# 03_-_RS232_JOYSTICK.net
KiCad netlist of a schematic drawn in Altium Designer
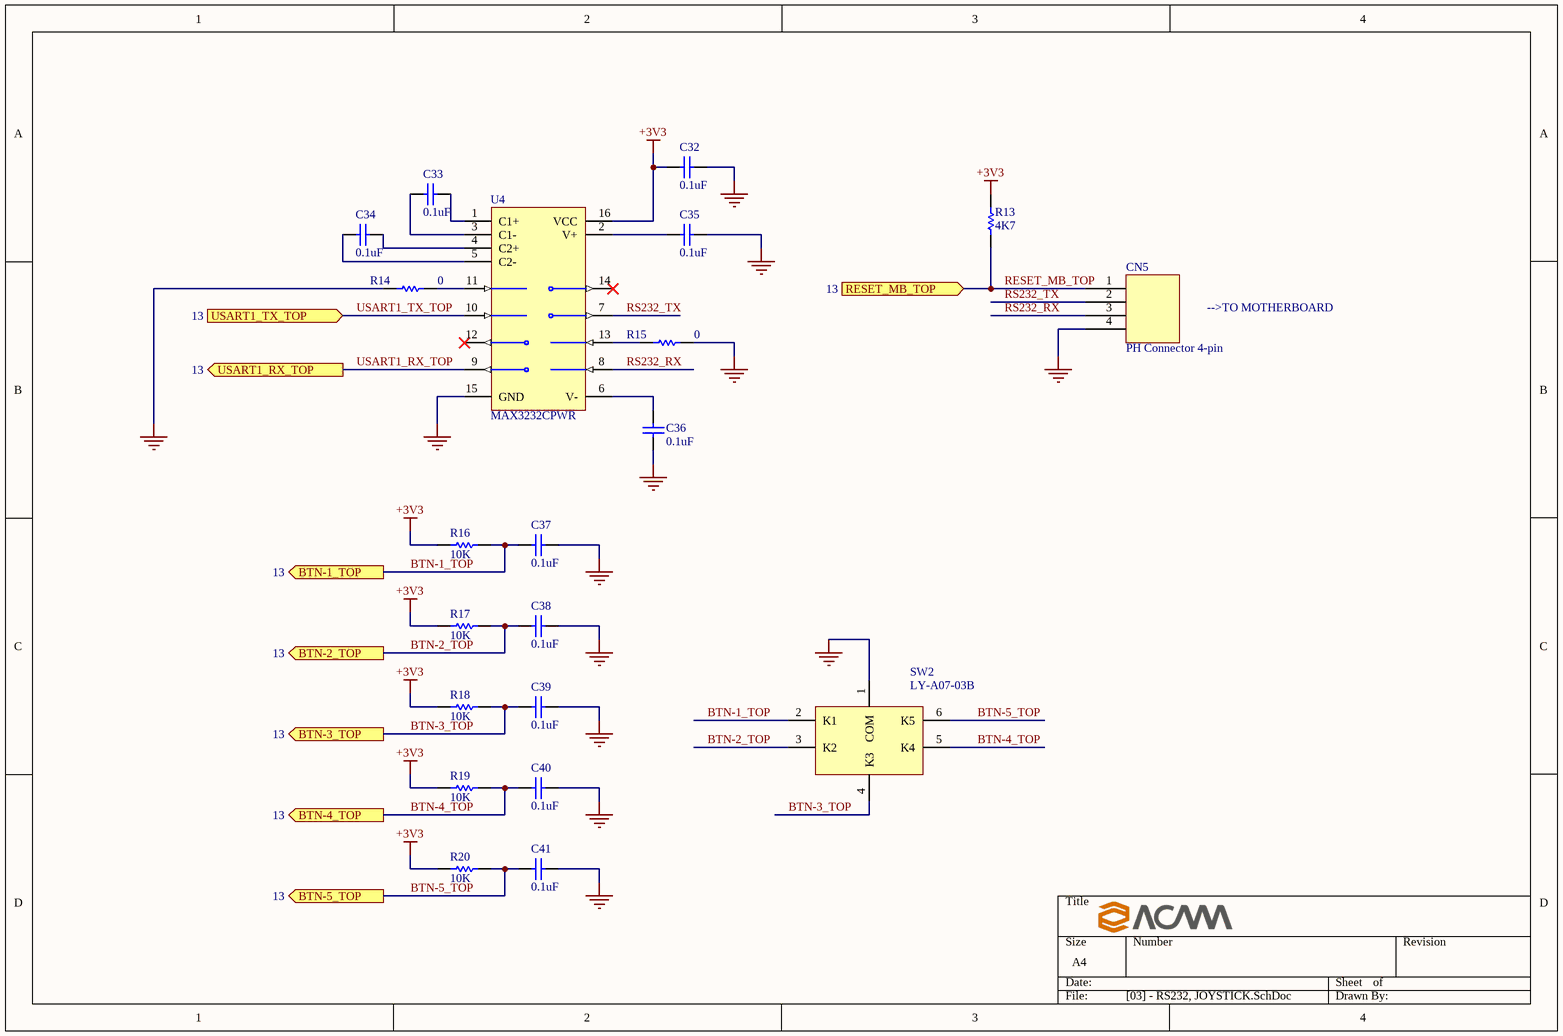
[diagram p0: [03] - RS232, JOYSTICK.SchDoc]

(export (version "E")
  (design (tool "Eeschema 10.0.6"))
  (components
    (comp (ref "C32")
      (value "0.1uF")
      (footprint "0805_C_AUTO")
      (description "Non-Pol SMD Capacitor")
      (libsource (lib "Farzan Custom Library") (part "Cap SMD"))
    )
    (comp (ref "C33")
      (value "0.1uF")
      (footprint "0805_C_AUTO")
      (description "Non-Pol SMD Capacitor")
      (libsource (lib "Farzan Custom Library") (part "Cap SMD"))
    )
    (comp (ref "C34")
      (value "0.1uF")
      (footprint "0805_C_AUTO")
      (description "Non-Pol SMD Capacitor")
      (libsource (lib "Farzan Custom Library") (part "Cap SMD"))
    )
    (comp (ref "C35")
      (value "0.1uF")
      (footprint "0805_C_AUTO")
      (description "Non-Pol SMD Capacitor")
      (libsource (lib "Farzan Custom Library") (part "Cap SMD"))
    )
    (comp (ref "C36")
      (value "0.1uF")
      (footprint "0805_C_AUTO")
      (description "Non-Pol SMD Capacitor")
      (libsource (lib "Farzan Custom Library") (part "Cap SMD"))
    )
    (comp (ref "C37")
      (value "0.1uF")
      (footprint "0805_C_AUTO")
      (description "Non-Pol SMD Capacitor")
      (libsource (lib "Farzan Custom Library") (part "Cap SMD"))
    )
    (comp (ref "C38")
      (value "0.1uF")
      (footprint "0805_C_AUTO")
      (description "Non-Pol SMD Capacitor")
      (libsource (lib "Farzan Custom Library") (part "Cap SMD"))
    )
    (comp (ref "C39")
      (value "0.1uF")
      (footprint "0805_C_AUTO")
      (description "Non-Pol SMD Capacitor")
      (libsource (lib "Farzan Custom Library") (part "Cap SMD"))
    )
    (comp (ref "C40")
      (value "0.1uF")
      (footprint "0805_C_AUTO")
      (description "Non-Pol SMD Capacitor")
      (libsource (lib "Farzan Custom Library") (part "Cap SMD"))
    )
    (comp (ref "C41")
      (value "0.1uF")
      (footprint "0805_C_AUTO")
      (description "Non-Pol SMD Capacitor")
      (libsource (lib "Farzan Custom Library") (part "Cap SMD"))
    )
    (comp (ref "CN5")
      (value "PH Connector 4-pin")
      (footprint "PH_4PIN")
      (description "PH Connector , 4 pin, 2mm pitch, straight")
      (libsource (lib "Farzan Custom Library") (part "PH Connector 4-pin"))
    )
    (comp (ref "R13")
      (value "4K7")
      (footprint "0805_R_AUTO")
      (description "SMD Resistor")
      (fields (field (name "TOLERANCE") "5%"))
      (libsource (lib "Farzan Custom Library") (part "Res SMD"))
    )
    (comp (ref "R14")
      (value "0")
      (footprint "0805_R_AUTO")
      (description "SMD Resistor")
      (fields (field (name "TOLERANCE") "5%"))
      (libsource (lib "Farzan Custom Library") (part "Res SMD"))
    )
    (comp (ref "R15")
      (value "0")
      (footprint "0805_R_AUTO")
      (description "SMD Resistor")
      (fields (field (name "TOLERANCE") "5%"))
      (libsource (lib "Farzan Custom Library") (part "Res SMD"))
    )
    (comp (ref "R16")
      (value "10K")
      (footprint "0805_R_AUTO")
      (description "SMD Resistor")
      (fields (field (name "TOLERANCE") "5%"))
      (libsource (lib "Farzan Custom Library") (part "Res SMD"))
    )
    (comp (ref "R17")
      (value "10K")
      (footprint "0805_R_AUTO")
      (description "SMD Resistor")
      (fields (field (name "TOLERANCE") "5%"))
      (libsource (lib "Farzan Custom Library") (part "Res SMD"))
    )
    (comp (ref "R18")
      (value "10K")
      (footprint "0805_R_AUTO")
      (description "SMD Resistor")
      (fields (field (name "TOLERANCE") "5%"))
      (libsource (lib "Farzan Custom Library") (part "Res SMD"))
    )
    (comp (ref "R19")
      (value "10K")
      (footprint "0805_R_AUTO")
      (description "SMD Resistor")
      (fields (field (name "TOLERANCE") "5%"))
      (libsource (lib "Farzan Custom Library") (part "Res SMD"))
    )
    (comp (ref "R20")
      (value "10K")
      (footprint "0805_R_AUTO")
      (description "SMD Resistor")
      (fields (field (name "TOLERANCE") "5%"))
      (libsource (lib "Farzan Custom Library") (part "Res SMD"))
    )
    (comp (ref "SW2")
      (value "LY-A07-03B")
      (footprint "LY-A07-03B")
      (description "5 Way Key")
      (libsource (lib "Farzan Custom Library") (part "KEY 5W"))
    )
    (comp (ref "U4")
      (value "MAX3232CPWR")
      (footprint "TSSOP-16")
      (description "3.0V TO 5.5V, Low-Power, up to 1Mbps, True RS-232 Transceiver Using Four 0.1µF External Capacitor")
      (libsource (lib "Farzan Custom Library") (part "MAX3232"))
    )
  )
  (nets
    (net (code "1") (name "+3V3") (class "Default")
      (node (ref "C32") (pin "2") (pinfunction "2_2") (pintype "passive"))
      (node (ref "R13") (pin "1") (pinfunction "1_1") (pintype "passive"))
      (node (ref "R16") (pin "2") (pinfunction "2_2") (pintype "passive"))
      (node (ref "R17") (pin "2") (pinfunction "2_2") (pintype "passive"))
      (node (ref "R18") (pin "2") (pinfunction "2_2") (pintype "passive"))
      (node (ref "R19") (pin "2") (pinfunction "2_2") (pintype "passive"))
      (node (ref "R20") (pin "2") (pinfunction "2_2") (pintype "passive"))
      (node (ref "U4") (pin "16") (pinfunction "VCC_16") (pintype "power_in"))
    )
    (net (code "2") (name "/BTN-1_TOP") (class "Default")
      (node (ref "C37") (pin "2") (pinfunction "2_2") (pintype "passive"))
      (node (ref "R16") (pin "1") (pinfunction "1_1") (pintype "passive"))
      (node (ref "SW2") (pin "2") (pinfunction "K1_2") (pintype "passive"))
    )
    (net (code "3") (name "/BTN-2_TOP") (class "Default")
      (node (ref "C38") (pin "2") (pinfunction "2_2") (pintype "passive"))
      (node (ref "R17") (pin "1") (pinfunction "1_1") (pintype "passive"))
      (node (ref "SW2") (pin "3") (pinfunction "K2_3") (pintype "passive"))
    )
    (net (code "4") (name "/BTN-3_TOP") (class "Default")
      (node (ref "C39") (pin "2") (pinfunction "2_2") (pintype "passive"))
      (node (ref "R18") (pin "1") (pinfunction "1_1") (pintype "passive"))
      (node (ref "SW2") (pin "4") (pinfunction "K3_4") (pintype "passive"))
    )
    (net (code "5") (name "/BTN-4_TOP") (class "Default")
      (node (ref "C40") (pin "2") (pinfunction "2_2") (pintype "passive"))
      (node (ref "R19") (pin "1") (pinfunction "1_1") (pintype "passive"))
      (node (ref "SW2") (pin "5") (pinfunction "K4_5") (pintype "passive"))
    )
    (net (code "6") (name "/BTN-5_TOP") (class "Default")
      (node (ref "C41") (pin "2") (pinfunction "2_2") (pintype "passive"))
      (node (ref "R20") (pin "1") (pinfunction "1_1") (pintype "passive"))
      (node (ref "SW2") (pin "6") (pinfunction "K5_6") (pintype "passive"))
    )
    (net (code "7") (name "/RESET_MB_TOP") (class "Default")
      (node (ref "CN5") (pin "1") (pinfunction "1_1") (pintype "passive"))
      (node (ref "R13") (pin "2") (pinfunction "2_2") (pintype "passive"))
    )
    (net (code "8") (name "/RS232_RX") (class "Default")
      (node (ref "CN5") (pin "3") (pinfunction "3_3") (pintype "passive"))
      (node (ref "U4") (pin "8") (pinfunction "R2IN_8") (pintype "input"))
    )
    (net (code "9") (name "/RS232_TX") (class "Default")
      (node (ref "CN5") (pin "2") (pinfunction "2_2") (pintype "passive"))
      (node (ref "U4") (pin "7") (pinfunction "T2OUT_7") (pintype "output"))
    )
    (net (code "10") (name "/USART1_RX_TOP") (class "Default")
      (node (ref "U4") (pin "9") (pinfunction "R2OUT_9") (pintype "output"))
    )
    (net (code "11") (name "/USART1_TX_TOP") (class "Default")
      (node (ref "U4") (pin "10") (pinfunction "T2IN_10") (pintype "input"))
    )
    (net (code "12") (name "GND") (class "Default")
      (node (ref "C32") (pin "1") (pinfunction "1_1") (pintype "passive"))
      (node (ref "C35") (pin "1") (pinfunction "1_1") (pintype "passive"))
      (node (ref "C36") (pin "1") (pinfunction "1_1") (pintype "passive"))
      (node (ref "C37") (pin "1") (pinfunction "1_1") (pintype "passive"))
      (node (ref "C38") (pin "1") (pinfunction "1_1") (pintype "passive"))
      (node (ref "C39") (pin "1") (pinfunction "1_1") (pintype "passive"))
      (node (ref "C40") (pin "1") (pinfunction "1_1") (pintype "passive"))
      (node (ref "C41") (pin "1") (pinfunction "1_1") (pintype "passive"))
      (node (ref "CN5") (pin "4") (pinfunction "4_4") (pintype "passive"))
      (node (ref "R14") (pin "1") (pinfunction "1_1") (pintype "passive"))
      (node (ref "R15") (pin "2") (pinfunction "2_2") (pintype "passive"))
      (node (ref "SW2") (pin "1") (pinfunction "COM_1") (pintype "passive"))
      (node (ref "U4") (pin "15") (pinfunction "GND_15") (pintype "power_in"))
    )
    (net (code "13") (name "Net-(U4-C1+)") (class "Default")
      (node (ref "C33") (pin "2") (pinfunction "2_2") (pintype "passive"))
      (node (ref "U4") (pin "1") (pinfunction "C1+_1") (pintype "passive"))
    )
    (net (code "14") (name "Net-(U4-C1-)") (class "Default")
      (node (ref "C33") (pin "1") (pinfunction "1_1") (pintype "passive"))
      (node (ref "U4") (pin "3") (pinfunction "C1-_3") (pintype "passive"))
    )
    (net (code "15") (name "Net-(U4-C2+)") (class "Default")
      (node (ref "C34") (pin "1") (pinfunction "1_1") (pintype "passive"))
      (node (ref "U4") (pin "4") (pinfunction "C2+_4") (pintype "passive"))
    )
    (net (code "16") (name "Net-(U4-C2-)") (class "Default")
      (node (ref "C34") (pin "2") (pinfunction "2_2") (pintype "passive"))
      (node (ref "U4") (pin "5") (pinfunction "C2-_5") (pintype "passive"))
    )
    (net (code "17") (name "Net-(U4-R1IN)") (class "Default")
      (node (ref "R15") (pin "1") (pinfunction "1_1") (pintype "passive"))
      (node (ref "U4") (pin "13") (pinfunction "R1IN_13") (pintype "input"))
    )
    (net (code "18") (name "Net-(U4-T1IN)") (class "Default")
      (node (ref "R14") (pin "2") (pinfunction "2_2") (pintype "passive"))
      (node (ref "U4") (pin "11") (pinfunction "T1IN_11") (pintype "input"))
    )
    (net (code "19") (name "Net-(U4-V+)") (class "Default")
      (node (ref "C35") (pin "2") (pinfunction "2_2") (pintype "passive"))
      (node (ref "U4") (pin "2") (pinfunction "V+_2") (pintype "power_in"))
    )
    (net (code "20") (name "Net-(U4-V-)") (class "Default")
      (node (ref "C36") (pin "2") (pinfunction "2_2") (pintype "passive"))
      (node (ref "U4") (pin "6") (pinfunction "V-_6") (pintype "power_in"))
    )
    (net (code "21") (name "unconnected-(U4-R1OUT-Pad12)") (class "Default")
      (node (ref "U4") (pin "12") (pinfunction "R1OUT_12") (pintype "output+no_connect"))
    )
    (net (code "22") (name "unconnected-(U4-T1OUT-Pad14)") (class "Default")
      (node (ref "U4") (pin "14") (pinfunction "T1OUT_14") (pintype "output+no_connect"))
    )
  )
)
